# Power.net
KiCad netlist of a schematic drawn in Altium Designer
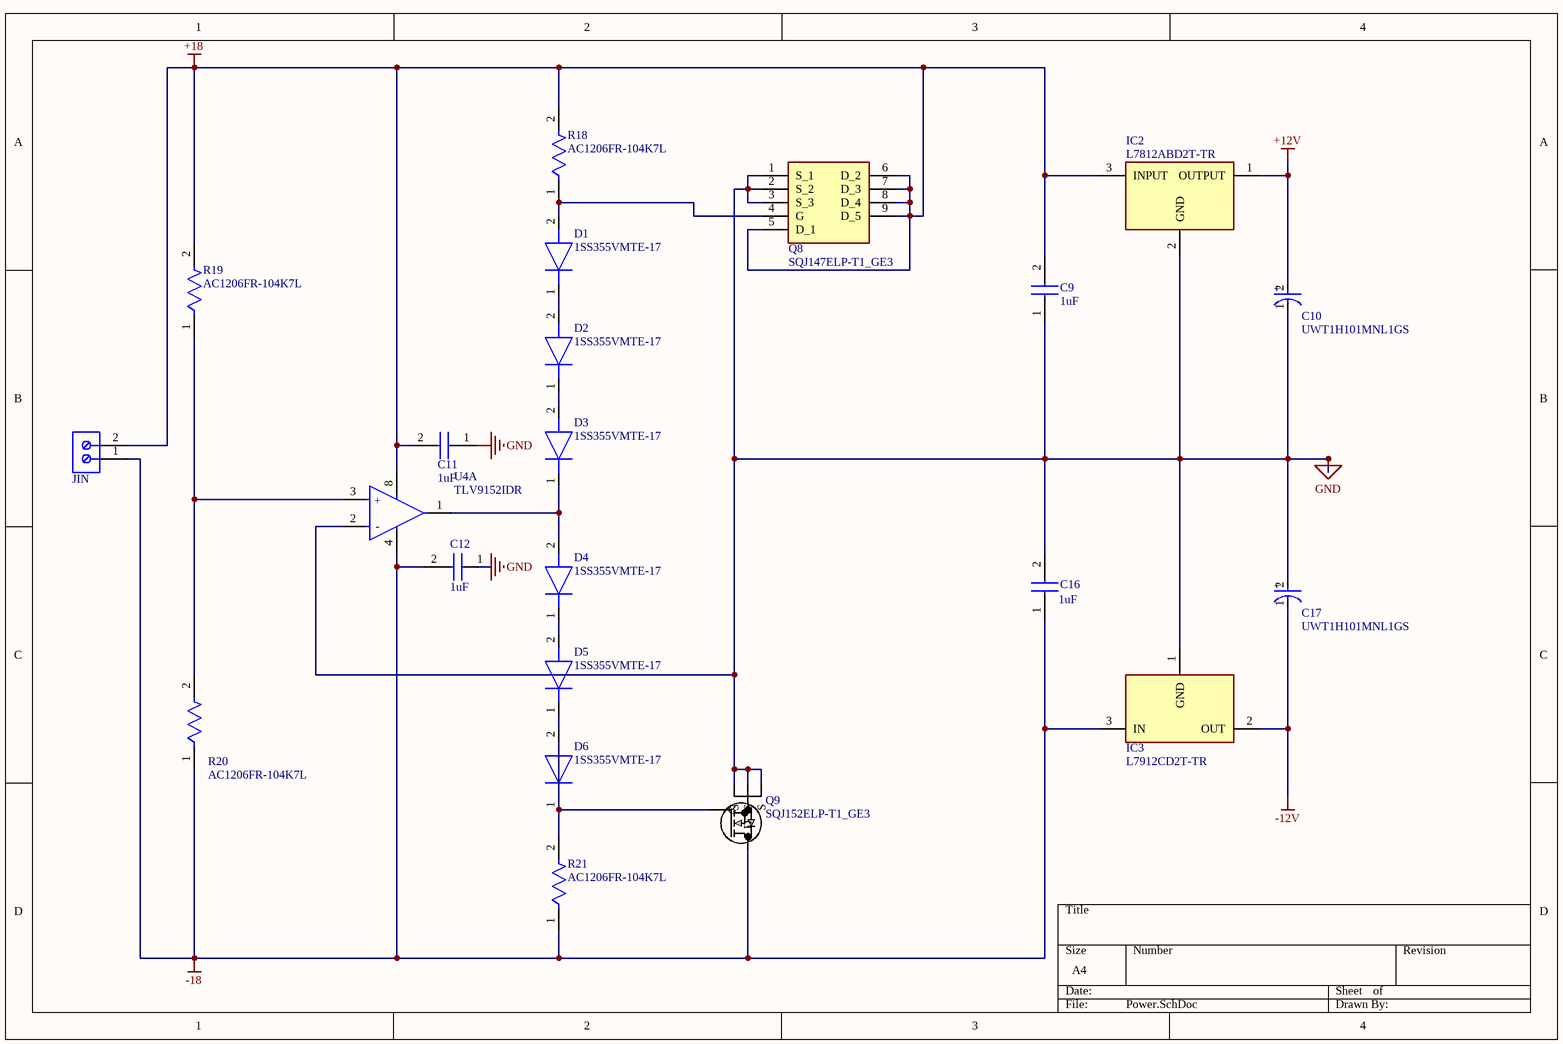
[diagram p0: Power.SchDoc]

(export (version "E")
  (design (tool "Eeschema 10.0.6"))
  (components
    (comp (ref "C9")
      (value "1uF")
      (footprint "SamacSys:CAPC3216X178N")
      (description "Capacitor 12063C105MAT2A")
      (fields
        (field (name "MANUFACTURER_PART_NUMBER") "12063C105MAT2A")
        (field (name "MOUSER PART NUMBER") "581-12063C105MAT2A")
      )
      (libsource (lib "*") (part "12063C105MAT2A"))
    )
    (comp (ref "C10")
      (value "UWT1H101MNL1GS")
      (footprint "FP-UWT1H101MNL1GS-MFG")
      (description "CAP ALUM 100UF 20% 50V SMD")
      (fields (field (name "TOLERANCE") "20%") (field (name "VOLTAGE") "50V"))
      (libsource (lib "Altium Content Vault") (part "203bc49f2ac43e59fd269a8c329ed05"))
    )
    (comp (ref "C11")
      (value "1uF")
      (footprint "SamacSys:CAPC3216X178N")
      (description "Capacitor 12063C105MAT2A")
      (fields
        (field (name "MANUFACTURER_PART_NUMBER") "12063C105MAT2A")
        (field (name "MOUSER PART NUMBER") "581-12063C105MAT2A")
      )
      (libsource (lib "*") (part "12063C105MAT2A"))
    )
    (comp (ref "C12")
      (value "1uF")
      (footprint "SamacSys:CAPC3216X178N")
      (description "Capacitor 12063C105MAT2A")
      (fields
        (field (name "MANUFACTURER_PART_NUMBER") "12063C105MAT2A")
        (field (name "MOUSER PART NUMBER") "581-12063C105MAT2A")
      )
      (libsource (lib "*") (part "12063C105MAT2A"))
    )
    (comp (ref "C16")
      (value "1uF")
      (footprint "SamacSys:CAPC3216X178N")
      (description "Capacitor 12063C105MAT2A")
      (fields
        (field (name "MANUFACTURER_PART_NUMBER") "12063C105MAT2A")
        (field (name "MOUSER PART NUMBER") "581-12063C105MAT2A")
      )
      (libsource (lib "*") (part "12063C105MAT2A"))
    )
    (comp (ref "C17")
      (value "UWT1H101MNL1GS")
      (footprint "FP-UWT1H101MNL1GS-MFG")
      (description "CAP ALUM 100UF 20% 50V SMD")
      (fields (field (name "TOLERANCE") "20%") (field (name "VOLTAGE") "50V"))
      (libsource (lib "Altium Content Vault") (part "203bc49f2ac43e59fd269a8c329ed05"))
    )
    (comp (ref "D1")
      (value "1SS355VMTE-17")
      (footprint "SamacSys:UDZVTE1722B")
      (description "Diode")
      (fields (field (name "MOUSER PART NUMBER") "755-1SS355VMTE-17"))
      (libsource (lib "SamacSys") (part "1SS355VMTE-17"))
    )
    (comp (ref "D2")
      (value "1SS355VMTE-17")
      (footprint "SamacSys:UDZVTE1722B")
      (description "Diode")
      (fields (field (name "MOUSER PART NUMBER") "755-1SS355VMTE-17"))
      (libsource (lib "SamacSys") (part "1SS355VMTE-17"))
    )
    (comp (ref "D3")
      (value "1SS355VMTE-17")
      (footprint "SamacSys:UDZVTE1722B")
      (description "Diode")
      (fields (field (name "MOUSER PART NUMBER") "755-1SS355VMTE-17"))
      (libsource (lib "SamacSys") (part "1SS355VMTE-17"))
    )
    (comp (ref "D4")
      (value "1SS355VMTE-17")
      (footprint "SamacSys:UDZVTE1722B")
      (description "Diode")
      (fields (field (name "MOUSER PART NUMBER") "755-1SS355VMTE-17"))
      (libsource (lib "SamacSys") (part "1SS355VMTE-17"))
    )
    (comp (ref "D5")
      (value "1SS355VMTE-17")
      (footprint "SamacSys:UDZVTE1722B")
      (description "Diode")
      (fields (field (name "MOUSER PART NUMBER") "755-1SS355VMTE-17"))
      (libsource (lib "SamacSys") (part "1SS355VMTE-17"))
    )
    (comp (ref "D6")
      (value "1SS355VMTE-17")
      (footprint "SamacSys:UDZVTE1722B")
      (description "Diode")
      (fields (field (name "MOUSER PART NUMBER") "755-1SS355VMTE-17"))
      (libsource (lib "SamacSys") (part "1SS355VMTE-17"))
    )
    (comp (ref "IC2")
      (value "L7812ABD2T-TR")
      (footprint "SamacSys:L7812ABD2TTR")
      (description "Integrated Circuit")
      (fields (field (name "MOUSER PART NUMBER") "511-L7812ABD2T-TR"))
      (libsource (lib "SamacSys") (part "L7812ABD2T-TR"))
    )
    (comp (ref "IC3")
      (value "L7912CD2T-TR")
      (footprint "SamacSys:L7905CD2TTR")
      (description "Integrated Circuit")
      (fields (field (name "MOUSER PART NUMBER") "511-L7912CD2T-TR"))
      (libsource (lib "SamacSys") (part "L7912CD2T-TR"))
    )
    (comp (ref "JIN")
      (value "1714955")
      (footprint "PHOE-1714955_V")
      (description "PC Terminal Block, Pitch 6.35 mm, 1 x 2 Position, Height 21.5 mm, Tail Lenght 5.1 mm, RoHS, Bulk")
      (fields (field (name "MANUFACTURER") "Phoenix Contact"))
      (libsource (lib "Altium Content Vault") (part "CN-1P-F-TB2"))
    )
    (comp (ref "Q8")
      (value "SQJ147ELP-T1_GE3")
      (footprint "SamacSys:SQJ147ELPT1_GE3")
      (description "MOSFET (N-Channel)")
      (fields (field (name "MOUSER PART NUMBER") "78-SQJ147ELP-T1_GE3"))
      (libsource (lib "*") (part "SQJ147ELP-T1_GE3"))
    )
    (comp (ref "Q9")
      (value "SQJ152ELP-T1_GE3")
      (footprint "DPAK5_ELP-T1_GE3_VIS")
      (description "No Description Available")
      (fields (field (name "COPYRIGHT") "Copyright (C) 2023 Ultra Librarian. All rights reserved."))
      (libsource (lib "SQJ152ELP-T1_GE3") (part "SQJ152ELP-T1_GE3"))
    )
    (comp (ref "R18")
      (value "AC1206FR-104K7L")
      (footprint "FP-AC1206-MFG")
      (description "AC1206 4.7KΩ 0.25W 1.00%")
      (fields
        (field (name "OCTOPART") "https://octopart.com/ac1206fr-104k7l-yageo-84718857")
        (field (name "TOLERANCE") "0.01")
      )
      (libsource (lib "Altium Content Vault") (part "1029c3af85768c4190bb7ad29bc67b5"))
    )
    (comp (ref "R19")
      (value "AC1206FR-104K7L")
      (footprint "FP-AC1206-MFG")
      (description "AC1206 4.7KΩ 0.25W 1.00%")
      (fields
        (field (name "OCTOPART") "https://octopart.com/ac1206fr-104k7l-yageo-84718857")
        (field (name "TOLERANCE") "0.01")
      )
      (libsource (lib "Altium Content Vault") (part "1029c3af85768c4190bb7ad29bc67b5"))
    )
    (comp (ref "R20")
      (value "AC1206FR-104K7L")
      (footprint "FP-AC1206-MFG")
      (description "AC1206 4.7KΩ 0.25W 1.00%")
      (fields
        (field (name "OCTOPART") "https://octopart.com/ac1206fr-104k7l-yageo-84718857")
        (field (name "TOLERANCE") "0.01")
      )
      (libsource (lib "Altium Content Vault") (part "1029c3af85768c4190bb7ad29bc67b5"))
    )
    (comp (ref "R21")
      (value "AC1206FR-104K7L")
      (footprint "FP-AC1206-MFG")
      (description "AC1206 4.7KΩ 0.25W 1.00%")
      (fields
        (field (name "OCTOPART") "https://octopart.com/ac1206fr-104k7l-yageo-84718857")
        (field (name "TOLERANCE") "0.01")
      )
      (libsource (lib "Altium Content Vault") (part "1029c3af85768c4190bb7ad29bc67b5"))
    )
    (comp (ref "U4")
      (value "TLV9152IDR")
      (footprint "FP-D0008A-IPC_A")
      (description "IC OPAMP GP 2 CIRCUIT 8SOIC")
      (libsource (lib "Altium Content Vault") (part "d5b36c1049528187b1d2197d5d58d7e"))
    )
  )
  (nets
    (net (code "1") (name "+12V") (class "Default")
      (node (ref "C10") (pin "2") (pinfunction "A_2") (pintype "passive"))
      (node (ref "IC2") (pin "1") (pinfunction "OUTPUT_1") (pintype "passive"))
    )
    (net (code "2") (name "+18") (class "Default")
      (node (ref "C11") (pin "2") (pinfunction "2_2") (pintype "passive"))
      (node (ref "C9") (pin "2") (pinfunction "2_2") (pintype "passive"))
      (node (ref "IC2") (pin "3") (pinfunction "INPUT_3") (pintype "passive"))
      (node (ref "JIN") (pin "2") (pinfunction "2_2") (pintype "passive"))
      (node (ref "Q8") (pin "5") (pinfunction "D_1_5") (pintype "passive"))
      (node (ref "Q8") (pin "6") (pinfunction "D_2_6") (pintype "passive"))
      (node (ref "Q8") (pin "7") (pinfunction "D_3_7") (pintype "passive"))
      (node (ref "Q8") (pin "8") (pinfunction "D_4_8") (pintype "passive"))
      (node (ref "Q8") (pin "9") (pinfunction "D_5_9") (pintype "passive"))
      (node (ref "R18") (pin "2") (pinfunction "2_2") (pintype "passive"))
      (node (ref "R19") (pin "2") (pinfunction "2_2") (pintype "passive"))
      (node (ref "U4") (pin "8") (pinfunction "V+_8") (pintype "power_in"))
    )
    (net (code "3") (name "-12V") (class "Default")
      (node (ref "C17") (pin "1") (pinfunction "C_1") (pintype "passive"))
      (node (ref "IC3") (pin "2") (pinfunction "OUT_2") (pintype "passive"))
    )
    (net (code "4") (name "-18") (class "Default")
      (node (ref "C12") (pin "2") (pinfunction "2_2") (pintype "passive"))
      (node (ref "C16") (pin "1") (pinfunction "1_1") (pintype "passive"))
      (node (ref "IC3") (pin "3") (pinfunction "IN_3") (pintype "passive"))
      (node (ref "JIN") (pin "1") (pinfunction "1_1") (pintype "passive"))
      (node (ref "Q9") (pin "5") (pinfunction "D_5") (pintype "passive"))
      (node (ref "R20") (pin "1") (pinfunction "1_1") (pintype "passive"))
      (node (ref "R21") (pin "1") (pinfunction "1_1") (pintype "passive"))
      (node (ref "U4") (pin "4") (pinfunction "V-_4") (pintype "power_in"))
    )
    (net (code "5") (name "GND") (class "Default")
      (node (ref "C10") (pin "1") (pinfunction "C_1") (pintype "passive"))
      (node (ref "C11") (pin "1") (pinfunction "1_1") (pintype "passive"))
      (node (ref "C12") (pin "1") (pinfunction "1_1") (pintype "passive"))
      (node (ref "C16") (pin "2") (pinfunction "2_2") (pintype "passive"))
      (node (ref "C17") (pin "2") (pinfunction "A_2") (pintype "passive"))
      (node (ref "C9") (pin "1") (pinfunction "1_1") (pintype "passive"))
      (node (ref "IC2") (pin "2") (pinfunction "GND_2") (pintype "passive"))
      (node (ref "IC3") (pin "1") (pinfunction "GND_1") (pintype "passive"))
      (node (ref "Q8") (pin "1") (pinfunction "S_1_1") (pintype "passive"))
      (node (ref "Q8") (pin "2") (pinfunction "S_2_2") (pintype "passive"))
      (node (ref "Q8") (pin "3") (pinfunction "S_3_3") (pintype "passive"))
      (node (ref "Q9") (pin "1") (pinfunction "S_1") (pintype "passive"))
      (node (ref "Q9") (pin "2") (pinfunction "S_2") (pintype "passive"))
      (node (ref "Q9") (pin "3") (pinfunction "S_3") (pintype "passive"))
      (node (ref "U4") (pin "2") (pinfunction "IN1-_2") (pintype "tri_state"))
    )
    (net (code "6") (name "Net-(D1-A)") (class "Default")
      (node (ref "D1") (pin "2") (pinfunction "A_2") (pintype "passive"))
      (node (ref "Q8") (pin "4") (pinfunction "G_4") (pintype "passive"))
      (node (ref "R18") (pin "1") (pinfunction "1_1") (pintype "passive"))
    )
    (net (code "7") (name "Net-(D1-K)") (class "Default")
      (node (ref "D1") (pin "1") (pinfunction "K_1") (pintype "passive"))
      (node (ref "D2") (pin "2") (pinfunction "A_2") (pintype "passive"))
    )
    (net (code "8") (name "Net-(D2-K)") (class "Default")
      (node (ref "D2") (pin "1") (pinfunction "K_1") (pintype "passive"))
      (node (ref "D3") (pin "2") (pinfunction "A_2") (pintype "passive"))
    )
    (net (code "9") (name "Net-(D3-K)") (class "Default")
      (node (ref "D3") (pin "1") (pinfunction "K_1") (pintype "passive"))
      (node (ref "D4") (pin "2") (pinfunction "A_2") (pintype "passive"))
      (node (ref "U4") (pin "1") (pinfunction "OUT1_1") (pintype "passive"))
    )
    (net (code "10") (name "Net-(D4-K)") (class "Default")
      (node (ref "D4") (pin "1") (pinfunction "K_1") (pintype "passive"))
      (node (ref "D5") (pin "2") (pinfunction "A_2") (pintype "passive"))
    )
    (net (code "11") (name "Net-(D5-K)") (class "Default")
      (node (ref "D5") (pin "1") (pinfunction "K_1") (pintype "passive"))
      (node (ref "D6") (pin "2") (pinfunction "A_2") (pintype "passive"))
    )
    (net (code "12") (name "Net-(D6-K)") (class "Default")
      (node (ref "D6") (pin "1") (pinfunction "K_1") (pintype "passive"))
      (node (ref "Q9") (pin "4") (pinfunction "G_4") (pintype "passive"))
      (node (ref "R21") (pin "2") (pinfunction "2_2") (pintype "passive"))
    )
    (net (code "13") (name "Net-(U4A-IN1+)") (class "Default")
      (node (ref "R19") (pin "1") (pinfunction "1_1") (pintype "passive"))
      (node (ref "R20") (pin "2") (pinfunction "2_2") (pintype "passive"))
      (node (ref "U4") (pin "3") (pinfunction "IN1+_3") (pintype "tri_state"))
    )
  )
)
